# PulseFit-THT.net
KiCad netlist of a schematic drawn in EAGLE
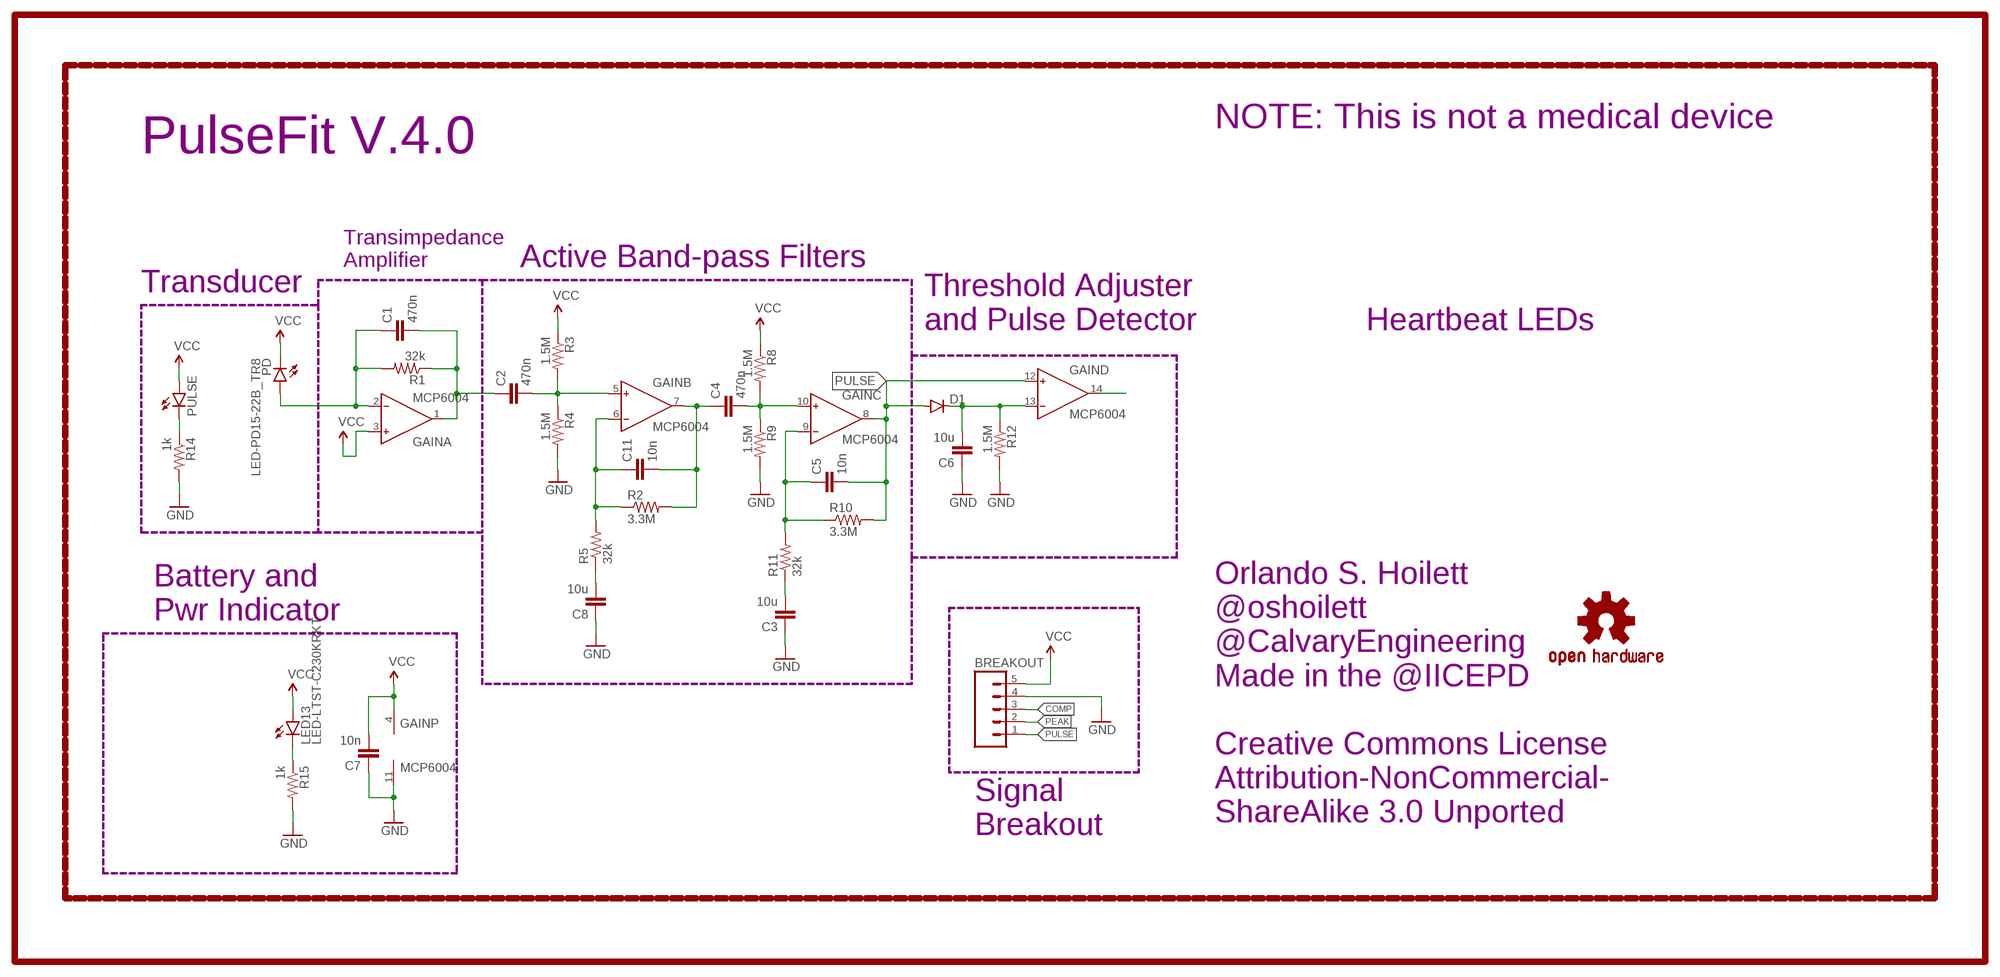
[diagram p0: schematic, sheet 1]

(export (version "E")
  (design (tool "Eeschema 10.0.6"))
  (components
    (comp (ref "BREAKOUT")
      (value "M05NO_SILK")
      (footprint "eagle-import:1X05_NO_SILK")
      (libsource (lib "eagle-import") (part "M05NO_SILK"))
    )
    (comp (ref "C1")
      (value "470n")
      (footprint "eagle-import:C0402")
      (libsource (lib "eagle-import") (part "C-EUC0402"))
    )
    (comp (ref "C2")
      (value "470n")
      (footprint "eagle-import:C0402")
      (libsource (lib "eagle-import") (part "C-EUC0402"))
    )
    (comp (ref "C3")
      (value "10u")
      (footprint "eagle-import:C0805")
      (libsource (lib "eagle-import") (part "C-EUC0805"))
    )
    (comp (ref "C4")
      (value "470n")
      (footprint "eagle-import:C0402")
      (libsource (lib "eagle-import") (part "C-EUC0402"))
    )
    (comp (ref "C5")
      (value "10n")
      (footprint "eagle-import:C0402")
      (libsource (lib "eagle-import") (part "C-EUC0402"))
    )
    (comp (ref "C6")
      (value "10u")
      (footprint "eagle-import:C0805")
      (libsource (lib "eagle-import") (part "C-EUC0805"))
    )
    (comp (ref "C7")
      (value "10n")
      (footprint "eagle-import:C0402")
      (libsource (lib "eagle-import") (part "C-EUC0402"))
    )
    (comp (ref "C8")
      (value "10u")
      (footprint "eagle-import:C0805")
      (libsource (lib "eagle-import") (part "C-EUC0805"))
    )
    (comp (ref "C11")
      (value "10n")
      (footprint "eagle-import:C0402")
      (libsource (lib "eagle-import") (part "C-EUC0402"))
    )
    (comp (ref "D1")
      (value "250mA/100V")
      (footprint "eagle-import:SOD-323")
      (libsource (lib "eagle-import") (part "DIODEBAS16"))
    )
    (comp (ref "GAIN")
      (value "MCP6004")
      (footprint "eagle-import:TSSOP14")
      (fields (field (name "MF") "ALTERA CORPORATION") (field (name "MPN") "AD8609ARUZ"))
      (libsource (lib "eagle-import") (part "AD8609RU"))
    )
    (comp (ref "LED13")
      (value "LED-LTST-C230KRKT")
      (footprint "eagle-import:LED-1206-BOTTOM")
      (libsource (lib "eagle-import") (part "LED-LTST-C230KRKT"))
    )
    (comp (ref "LOGO1")
      (value "OSHW-LOGOS")
      (footprint "eagle-import:OSHW-LOGO-S")
      (libsource (lib "eagle-import") (part "OSHW-LOGOS"))
    )
    (comp (ref "PD")
      (value "LED-PD15-22B_TR8")
      (footprint "eagle-import:LED-PD15-22B_TR8")
      (libsource (lib "eagle-import") (part "LED-PD15-22B_TR8"))
    )
    (comp (ref "PULSE")
      (value "LED0603")
      (footprint "eagle-import:LED-0603")
      (libsource (lib "eagle-import") (part "LED0603"))
    )
    (comp (ref "R1")
      (value "32k")
      (footprint "eagle-import:R0402")
      (libsource (lib "eagle-import") (part "R-US_R0402"))
    )
    (comp (ref "R2")
      (value "3.3M")
      (footprint "eagle-import:R0402")
      (libsource (lib "eagle-import") (part "R-US_R0402"))
    )
    (comp (ref "R3")
      (value "1.5M")
      (footprint "eagle-import:R0402")
      (libsource (lib "eagle-import") (part "R-US_R0402"))
    )
    (comp (ref "R4")
      (value "1.5M")
      (footprint "eagle-import:R0402")
      (libsource (lib "eagle-import") (part "R-US_R0402"))
    )
    (comp (ref "R5")
      (value "32k")
      (footprint "eagle-import:R0402")
      (libsource (lib "eagle-import") (part "R-US_R0402"))
    )
    (comp (ref "R8")
      (value "1.5M")
      (footprint "eagle-import:R0402")
      (libsource (lib "eagle-import") (part "R-US_R0402"))
    )
    (comp (ref "R9")
      (value "1.5M")
      (footprint "eagle-import:R0402")
      (libsource (lib "eagle-import") (part "R-US_R0402"))
    )
    (comp (ref "R10")
      (value "3.3M")
      (footprint "eagle-import:R0402")
      (libsource (lib "eagle-import") (part "R-US_R0402"))
    )
    (comp (ref "R11")
      (value "32k")
      (footprint "eagle-import:R0402")
      (libsource (lib "eagle-import") (part "R-US_R0402"))
    )
    (comp (ref "R12")
      (value "1.5M")
      (footprint "eagle-import:R0402")
      (libsource (lib "eagle-import") (part "R-US_R0402"))
    )
    (comp (ref "R14")
      (value "1k")
      (footprint "eagle-import:R0402")
      (libsource (lib "eagle-import") (part "R-US_R0402"))
    )
    (comp (ref "R15")
      (value "1k")
      (footprint "eagle-import:R0402")
      (libsource (lib "eagle-import") (part "R-US_R0402"))
    )
  )
  (nets
    (net (code "1") (name "COMP") (class "Default")
      (node (ref "BREAKOUT") (pin "3") (pinfunction "3_3") (pintype "passive"))
      (node (ref "GAIN") (pin "14") (pinfunction "OUT_14") (pintype "output"))
    )
    (net (code "2") (name "GND") (class "Default")
      (node (ref "BREAKOUT") (pin "4") (pinfunction "4_4") (pintype "passive"))
      (node (ref "C3") (pin "1") (pinfunction "1_1") (pintype "passive"))
      (node (ref "C6") (pin "1") (pinfunction "1_1") (pintype "passive"))
      (node (ref "C7") (pin "1") (pinfunction "1_1") (pintype "passive"))
      (node (ref "C8") (pin "1") (pinfunction "1_1") (pintype "passive"))
      (node (ref "GAIN") (pin "11") (pinfunction "V-_11") (pintype "power_in"))
      (node (ref "R12") (pin "2") (pinfunction "2_2") (pintype "passive"))
      (node (ref "R14") (pin "2") (pinfunction "2_2") (pintype "passive"))
      (node (ref "R15") (pin "2") (pinfunction "2_2") (pintype "passive"))
      (node (ref "R4") (pin "2") (pinfunction "2_2") (pintype "passive"))
      (node (ref "R9") (pin "2") (pinfunction "2_2") (pintype "passive"))
    )
    (net (code "3") (name "Net-(C3-Pad2)") (class "Default")
      (node (ref "C3") (pin "2") (pinfunction "2_2") (pintype "passive"))
      (node (ref "R11") (pin "1") (pinfunction "1_1") (pintype "passive"))
    )
    (net (code "4") (name "Net-(C8-Pad2)") (class "Default")
      (node (ref "C8") (pin "2") (pinfunction "2_2") (pintype "passive"))
      (node (ref "R5") (pin "1") (pinfunction "1_1") (pintype "passive"))
    )
    (net (code "5") (name "Net-(GAINA-IN-)") (class "Default")
      (node (ref "C1") (pin "1") (pinfunction "1_1") (pintype "passive"))
      (node (ref "GAIN") (pin "2") (pinfunction "IN-_2") (pintype "input"))
      (node (ref "PD") (pin "A-1") (pinfunction "A_A-1") (pintype "passive"))
      (node (ref "PD") (pin "A-2") (pinfunction "A_A-2") (pintype "passive"))
      (node (ref "R1") (pin "2") (pinfunction "2_2") (pintype "passive"))
    )
    (net (code "6") (name "Net-(GAINA-OUT)") (class "Default")
      (node (ref "C1") (pin "2") (pinfunction "2_2") (pintype "passive"))
      (node (ref "C2") (pin "1") (pinfunction "1_1") (pintype "passive"))
      (node (ref "GAIN") (pin "1") (pinfunction "OUT_1") (pintype "output"))
      (node (ref "R1") (pin "1") (pinfunction "1_1") (pintype "passive"))
    )
    (net (code "7") (name "Net-(GAINB-IN+)") (class "Default")
      (node (ref "C2") (pin "2") (pinfunction "2_2") (pintype "passive"))
      (node (ref "GAIN") (pin "5") (pinfunction "IN+_5") (pintype "input"))
      (node (ref "R3") (pin "2") (pinfunction "2_2") (pintype "passive"))
      (node (ref "R4") (pin "1") (pinfunction "1_1") (pintype "passive"))
    )
    (net (code "8") (name "Net-(GAINB-IN-)") (class "Default")
      (node (ref "C11") (pin "1") (pinfunction "1_1") (pintype "passive"))
      (node (ref "GAIN") (pin "6") (pinfunction "IN-_6") (pintype "input"))
      (node (ref "R2") (pin "1") (pinfunction "1_1") (pintype "passive"))
      (node (ref "R5") (pin "2") (pinfunction "2_2") (pintype "passive"))
    )
    (net (code "9") (name "Net-(GAINB-OUT)") (class "Default")
      (node (ref "C11") (pin "2") (pinfunction "2_2") (pintype "passive"))
      (node (ref "C4") (pin "1") (pinfunction "1_1") (pintype "passive"))
      (node (ref "GAIN") (pin "7") (pinfunction "OUT_7") (pintype "output"))
      (node (ref "R2") (pin "2") (pinfunction "2_2") (pintype "passive"))
    )
    (net (code "10") (name "Net-(GAINC-IN+)") (class "Default")
      (node (ref "C4") (pin "2") (pinfunction "2_2") (pintype "passive"))
      (node (ref "GAIN") (pin "10") (pinfunction "IN+_10") (pintype "input"))
      (node (ref "R8") (pin "2") (pinfunction "2_2") (pintype "passive"))
      (node (ref "R9") (pin "1") (pinfunction "1_1") (pintype "passive"))
    )
    (net (code "11") (name "Net-(GAINC-IN-)") (class "Default")
      (node (ref "C5") (pin "1") (pinfunction "1_1") (pintype "passive"))
      (node (ref "GAIN") (pin "9") (pinfunction "IN-_9") (pintype "input"))
      (node (ref "R10") (pin "1") (pinfunction "1_1") (pintype "passive"))
      (node (ref "R11") (pin "2") (pinfunction "2_2") (pintype "passive"))
    )
    (net (code "12") (name "Net-(LED13-PadC)") (class "Default")
      (node (ref "LED13") (pin "C") (pinfunction "C_C") (pintype "passive"))
      (node (ref "R15") (pin "1") (pinfunction "1_1") (pintype "passive"))
    )
    (net (code "13") (name "Net-(PULSE-PadC)") (class "Default")
      (node (ref "PULSE") (pin "C") (pinfunction "C_C") (pintype "passive"))
      (node (ref "R14") (pin "1") (pinfunction "1_1") (pintype "passive"))
    )
    (net (code "14") (name "PEAK") (class "Default")
      (node (ref "BREAKOUT") (pin "2") (pinfunction "2_2") (pintype "passive"))
      (node (ref "C6") (pin "2") (pinfunction "2_2") (pintype "passive"))
      (node (ref "D1") (pin "C") (pinfunction "C_C") (pintype "passive"))
      (node (ref "GAIN") (pin "13") (pinfunction "IN-_13") (pintype "input"))
      (node (ref "R12") (pin "1") (pinfunction "1_1") (pintype "passive"))
    )
    (net (code "15") (name "PULSE") (class "Default")
      (node (ref "BREAKOUT") (pin "1") (pinfunction "1_1") (pintype "passive"))
      (node (ref "C5") (pin "2") (pinfunction "2_2") (pintype "passive"))
      (node (ref "D1") (pin "A") (pinfunction "A_A") (pintype "passive"))
      (node (ref "GAIN") (pin "12") (pinfunction "IN+_12") (pintype "input"))
      (node (ref "GAIN") (pin "8") (pinfunction "OUT_8") (pintype "output"))
      (node (ref "R10") (pin "2") (pinfunction "2_2") (pintype "passive"))
    )
    (net (code "16") (name "VCC") (class "Default")
      (node (ref "BREAKOUT") (pin "5") (pinfunction "5_5") (pintype "passive"))
      (node (ref "C7") (pin "2") (pinfunction "2_2") (pintype "passive"))
      (node (ref "GAIN") (pin "3") (pinfunction "IN+_3") (pintype "input"))
      (node (ref "GAIN") (pin "4") (pinfunction "V+_4") (pintype "power_in"))
      (node (ref "LED13") (pin "A") (pinfunction "A_A") (pintype "passive"))
      (node (ref "PD") (pin "C-1") (pinfunction "C_C-1") (pintype "passive"))
      (node (ref "PD") (pin "C-2") (pinfunction "C_C-2") (pintype "passive"))
      (node (ref "PULSE") (pin "A") (pinfunction "A_A") (pintype "passive"))
      (node (ref "R3") (pin "1") (pinfunction "1_1") (pintype "passive"))
      (node (ref "R8") (pin "1") (pinfunction "1_1") (pintype "passive"))
    )
  )
)
